# 90_CAN.net
KiCad netlist of a schematic drawn in Altium Designer
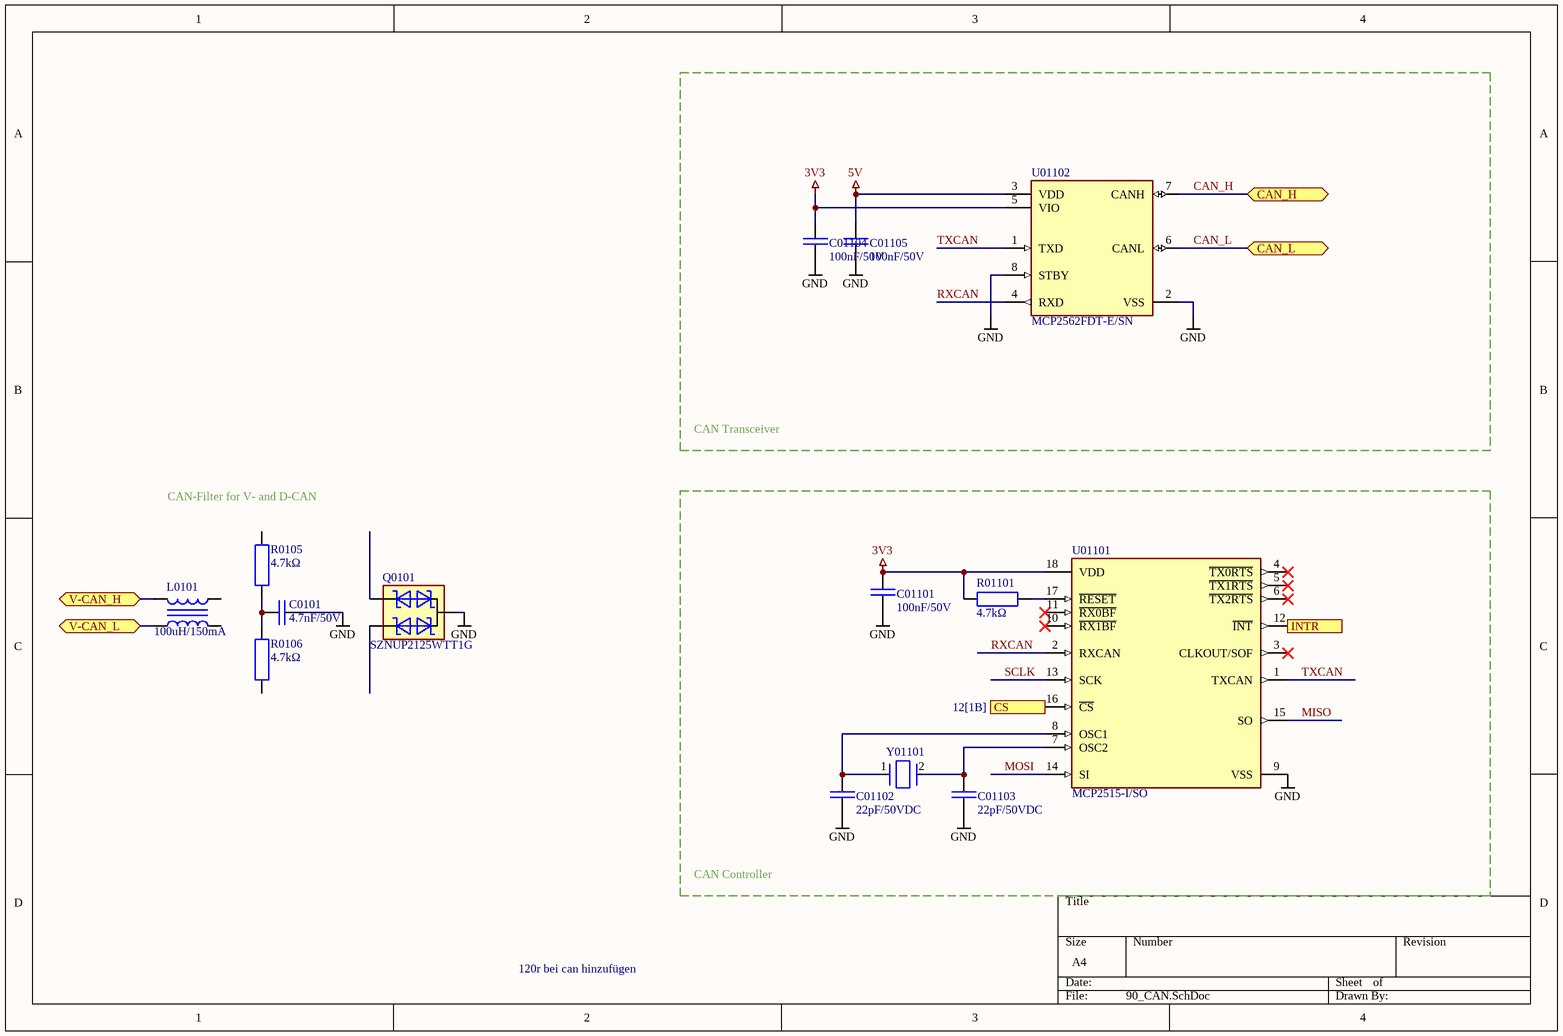
[diagram p0: 90_CAN.SchDoc]

(export (version "E")
  (design (tool "Eeschema 10.0.6"))
  (components
    (comp (ref "C0101")
      (value "4.7nF/50V")
      (footprint "CS_EIA0603_H1.00")
      (fields
        (field (name "PART NUMBER") "2132")
        (field (name "MANUFACTURER PART NUMBER") "C0603C472K5RACAUTO")
        (field (name "LIBCARE CREATE") "dz, 09.10.2018")
      )
      (libsource (lib "BRUSA_AltiumLib") (part "Capacitor"))
    )
    (comp (ref "C01101")
      (value "100nF/50V")
      (footprint "CS_EIA0603_H0.90")
      (fields
        (field (name "PART NUMBER") "4686")
        (field (name "MANUFACTURER PART NUMBER") "AC0603KRX7R9BB104")
        (field (name "MANUFACTURER") "YAGEO")
        (field (name "LIBCARE CREATE") "ct, 31.08.2021")
      )
      (libsource (lib "BRUSA_AltiumLib") (part "Capacitor"))
    )
    (comp (ref "C01102")
      (value "22pF/50VDC")
      (footprint "CS_EIA0603_H0.90")
      (fields
        (field (name "PART NUMBER") "3844")
        (field (name "MANUFACTURER PART NUMBER") "GCM1885C1H220JA16D")
        (field (name "MANUFACTURER") "MURATA")
        (field (name "LIBCARE CREATE") "Illya L., 16.08.2022        ,ema11")
      )
      (libsource (lib "BRUSA_AltiumLib") (part "Capacitor"))
    )
    (comp (ref "C01103")
      (value "22pF/50VDC")
      (footprint "CS_EIA0603_H0.90")
      (fields
        (field (name "PART NUMBER") "3844")
        (field (name "MANUFACTURER PART NUMBER") "GCM1885C1H220JA16D")
        (field (name "MANUFACTURER") "MURATA")
        (field (name "LIBCARE CREATE") "Illya L., 16.08.2022        ,ema11")
      )
      (libsource (lib "BRUSA_AltiumLib") (part "Capacitor"))
    )
    (comp (ref "C01104")
      (value "100nF/50V")
      (footprint "CS_EIA0603_H0.90")
      (fields
        (field (name "PART NUMBER") "4686")
        (field (name "MANUFACTURER PART NUMBER") "AC0603KRX7R9BB104")
        (field (name "MANUFACTURER") "YAGEO")
        (field (name "LIBCARE CREATE") "ct, 31.08.2021")
      )
      (libsource (lib "BRUSA_AltiumLib") (part "Capacitor"))
    )
    (comp (ref "C01105")
      (value "100nF/50V")
      (footprint "CS_EIA0603_H0.90")
      (fields
        (field (name "PART NUMBER") "4686")
        (field (name "MANUFACTURER PART NUMBER") "AC0603KRX7R9BB104")
        (field (name "MANUFACTURER") "YAGEO")
        (field (name "LIBCARE CREATE") "ct, 31.08.2021")
      )
      (libsource (lib "BRUSA_AltiumLib") (part "Capacitor"))
    )
    (comp (ref "L0101")
      (value "100uH/150mA")
      (footprint "ACT45B_TDK")
      (fields
        (field (name "PART NUMBER") "2761")
        (field (name "MANUFACTURER PART NUMBER") "ACT45B-101-2P-TL003")
        (field (name "LIBCARE CREATE") "dz, 27.07.2020")
      )
      (libsource (lib "BRUSA_AltiumLib") (part "ACT45B"))
    )
    (comp (ref "Q0101")
      (value "SZNUP2125WTT1G")
      (footprint "SOT-323_ON_SEMICONDUCTOR")
      (fields
        (field (name "PART NUMBER") "3643")
        (field (name "MANUFACTURER") "ONSEMI")
        (field (name "LIBCARE CREATE") "pr, 22.06.2022")
      )
      (libsource (lib "BRUSA_AltiumLib") (part "SZNUP2125WTT1G"))
    )
    (comp (ref "R0105")
      (value "4.7kΩ")
      (footprint "RS_EIA1206_H0.70")
      (description "SMD 4.7 kOhms 250 mW 1206 1%")
      (fields
        (field (name "MANUFACTURER") "YAGEO")
        (field (name "MANUFACTURER PART NUMBER") "AC1206FR-074K7L")
      )
      (libsource (lib "ProjectLib") (part "AC1206FR-074K7L"))
    )
    (comp (ref "R0106")
      (value "4.7kΩ")
      (footprint "RS_EIA1206_H0.70")
      (description "SMD 4.7 kOhms 250 mW 1206 1%")
      (fields
        (field (name "MANUFACTURER") "YAGEO")
        (field (name "MANUFACTURER PART NUMBER") "AC1206FR-074K7L")
      )
      (libsource (lib "ProjectLib") (part "AC1206FR-074K7L"))
    )
    (comp (ref "R01101")
      (value "4.7kΩ")
      (footprint "RS_EIA0603_H0.60")
      (fields
        (field (name "PART NUMBER") "3222")
        (field (name "MANUFACTURER PART NUMBER") "AC0603FR-074K7L")
        (field (name "MANUFACTURER") "YAGEO")
        (field (name "LIBCARE CREATE") "ct, 02.09.2021")
      )
      (libsource (lib "BRUSA_AltiumLib") (part "Resistor"))
    )
    (comp (ref "U01101")
      (value "MCP2515-I/SO")
      (footprint "FP-C04-051-MFG")
      (description "IC CAN CONTROLLER W/SPI 18SOIC")
      (fields
        (field (name "MANUFACTURER") "Microchip")
        (field (name "OCTOPART") "https://octopart.com/mcp2515-i%2Fso-microchip-430187")
      )
      (libsource (lib "Altium Content Vault") (part "1c78ea6ff576bac94664e2637e1b479"))
    )
    (comp (ref "U01102")
      (value "MCP2562FDT-E/SN")
      (footprint "FP-C04-057-SN-MFG")
      (description "IC TRANSCEIVER 1/1 8SOIC")
      (libsource (lib "Altium Content Vault") (part "fcb6c66e4429206983adab9201371df"))
    )
    (comp (ref "Y01101")
      (value "ABLS-16.000MHZ-K4T")
      (footprint "FP-ABLS-MFG")
      (description "CRYSTAL 16.0000MHZ 18PF SMD")
      (fields
        (field (name "TOLERANCE") "30ppm")
        (field (name "OCTOPART") "https://octopart.com/abls-16.000mhz-k4t-abracon-18618626")
      )
      (libsource (lib "Altium Content Vault") (part "c23a69dc6c9e2f18f2079038eb95dd1"))
    )
  )
  (nets
    (net (code "1") (name "/CAN_H") (class "Default")
      (node (ref "U01102") (pin "7") (pinfunction "CANH_7") (pintype "bidirectional"))
    )
    (net (code "2") (name "/CAN_L") (class "Default")
      (node (ref "U01102") (pin "6") (pinfunction "CANL_6") (pintype "bidirectional"))
    )
    (net (code "3") (name "/CS") (class "Default")
      (node (ref "U01101") (pin "16") (pinfunction "~{CS}_16") (pintype "input"))
    )
    (net (code "4") (name "/INTR") (class "Default")
      (node (ref "U01101") (pin "12") (pinfunction "~{INT}_12") (pintype "output"))
    )
    (net (code "5") (name "/MISO") (class "Default")
      (node (ref "U01101") (pin "15") (pinfunction "SO_15") (pintype "output"))
    )
    (net (code "6") (name "/MOSI") (class "Default")
      (node (ref "U01101") (pin "14") (pinfunction "SI_14") (pintype "input"))
    )
    (net (code "7") (name "/RXCAN") (class "Default")
      (node (ref "U01101") (pin "2") (pinfunction "RXCAN_2") (pintype "input"))
      (node (ref "U01102") (pin "4") (pinfunction "RXD_4") (pintype "output"))
    )
    (net (code "8") (name "/SCLK") (class "Default")
      (node (ref "U01101") (pin "13") (pinfunction "SCK_13") (pintype "input"))
    )
    (net (code "9") (name "/TXCAN") (class "Default")
      (node (ref "U01101") (pin "1") (pinfunction "TXCAN_1") (pintype "output"))
      (node (ref "U01102") (pin "1") (pinfunction "TXD_1") (pintype "input"))
    )
    (net (code "10") (name "/V-CAN_H") (class "Default")
      (node (ref "L0101") (pin "2") (pinfunction "2_2") (pintype "passive"))
    )
    (net (code "11") (name "/V-CAN_L") (class "Default")
      (node (ref "L0101") (pin "1") (pinfunction "1_1") (pintype "passive"))
    )
    (net (code "12") (name "3V3") (class "Default")
      (node (ref "C01101") (pin "1") (pintype "passive"))
      (node (ref "C01104") (pin "1") (pintype "passive"))
      (node (ref "R01101") (pin "2") (pintype "passive"))
      (node (ref "U01101") (pin "18") (pinfunction "VDD_18") (pintype "power_in"))
      (node (ref "U01102") (pin "5") (pinfunction "VIO_5") (pintype "power_in"))
    )
    (net (code "13") (name "5V") (class "Default")
      (node (ref "C01105") (pin "1") (pintype "passive"))
      (node (ref "U01102") (pin "3") (pinfunction "VDD_3") (pintype "power_in"))
    )
    (net (code "14") (name "GND") (class "Default")
      (node (ref "C0101") (pin "2") (pintype "passive"))
      (node (ref "C01101") (pin "2") (pintype "passive"))
      (node (ref "C01102") (pin "1") (pintype "passive"))
      (node (ref "C01103") (pin "1") (pintype "passive"))
      (node (ref "C01104") (pin "2") (pintype "passive"))
      (node (ref "C01105") (pin "2") (pintype "passive"))
      (node (ref "Q0101") (pin "3") (pintype "passive"))
      (node (ref "U01101") (pin "9") (pinfunction "VSS_9") (pintype "power_in"))
      (node (ref "U01102") (pin "2") (pinfunction "VSS_2") (pintype "power_in"))
      (node (ref "U01102") (pin "8") (pinfunction "STBY_8") (pintype "input"))
    )
    (net (code "15") (name "Net-(C0101-Pad1)") (class "Default")
      (node (ref "C0101") (pin "1") (pintype "passive"))
      (node (ref "R0105") (pin "1") (pintype "passive"))
      (node (ref "R0106") (pin "1") (pintype "passive"))
    )
    (net (code "16") (name "Net-(U01101-OSC1)") (class "Default")
      (node (ref "C01102") (pin "2") (pintype "passive"))
      (node (ref "U01101") (pin "8") (pinfunction "OSC1_8") (pintype "input"))
      (node (ref "Y01101") (pin "1") (pinfunction "1_1") (pintype "passive"))
    )
    (net (code "17") (name "Net-(U01101-OSC2)") (class "Default")
      (node (ref "C01103") (pin "2") (pintype "passive"))
      (node (ref "U01101") (pin "7") (pinfunction "OSC2_7") (pintype "input"))
      (node (ref "Y01101") (pin "2") (pinfunction "2_2") (pintype "passive"))
    )
    (net (code "18") (name "Net-(U01101-~{RESET})") (class "Default")
      (node (ref "R01101") (pin "1") (pintype "passive"))
      (node (ref "U01101") (pin "17") (pinfunction "~{RESET}_17") (pintype "input"))
    )
    (net (code "19") (name "unconnected-(L0101-Pad3)") (class "Default")
      (node (ref "L0101") (pin "3") (pinfunction "3_3") (pintype "passive"))
    )
    (net (code "20") (name "unconnected-(L0101-Pad4)") (class "Default")
      (node (ref "L0101") (pin "4") (pinfunction "4_4") (pintype "passive"))
    )
    (net (code "21") (name "unconnected-(Q0101-Pad1)") (class "Default")
      (node (ref "Q0101") (pin "1") (pintype "passive"))
    )
    (net (code "22") (name "unconnected-(Q0101-Pad2)") (class "Default")
      (node (ref "Q0101") (pin "2") (pintype "passive"))
    )
    (net (code "23") (name "unconnected-(R0105-Pad2)") (class "Default")
      (node (ref "R0105") (pin "2") (pintype "passive"))
    )
    (net (code "24") (name "unconnected-(R0106-Pad2)") (class "Default")
      (node (ref "R0106") (pin "2") (pintype "passive"))
    )
    (net (code "25") (name "unconnected-(U01101-CLKOUT{slash}SOF-Pad3)") (class "Default")
      (node (ref "U01101") (pin "3") (pinfunction "CLKOUT/SOF_3") (pintype "output+no_connect"))
    )
    (net (code "26") (name "unconnected-(U01101-~{RX0BF}-Pad11)") (class "Default")
      (node (ref "U01101") (pin "11") (pinfunction "~{RX0BF}_11") (pintype "input+no_connect"))
    )
    (net (code "27") (name "unconnected-(U01101-~{RX1BF}-Pad10)") (class "Default")
      (node (ref "U01101") (pin "10") (pinfunction "~{RX1BF}_10") (pintype "input+no_connect"))
    )
    (net (code "28") (name "unconnected-(U01101-~{TX0RTS}-Pad4)") (class "Default")
      (node (ref "U01101") (pin "4") (pinfunction "~{TX0RTS}_4") (pintype "output+no_connect"))
    )
    (net (code "29") (name "unconnected-(U01101-~{TX1RTS}-Pad5)") (class "Default")
      (node (ref "U01101") (pin "5") (pinfunction "~{TX1RTS}_5") (pintype "output+no_connect"))
    )
    (net (code "30") (name "unconnected-(U01101-~{TX2RTS}-Pad6)") (class "Default")
      (node (ref "U01101") (pin "6") (pinfunction "~{TX2RTS}_6") (pintype "output+no_connect"))
    )
  )
)
